# Battery_Prtection.net
KiCad netlist of a schematic drawn in Altium Designer
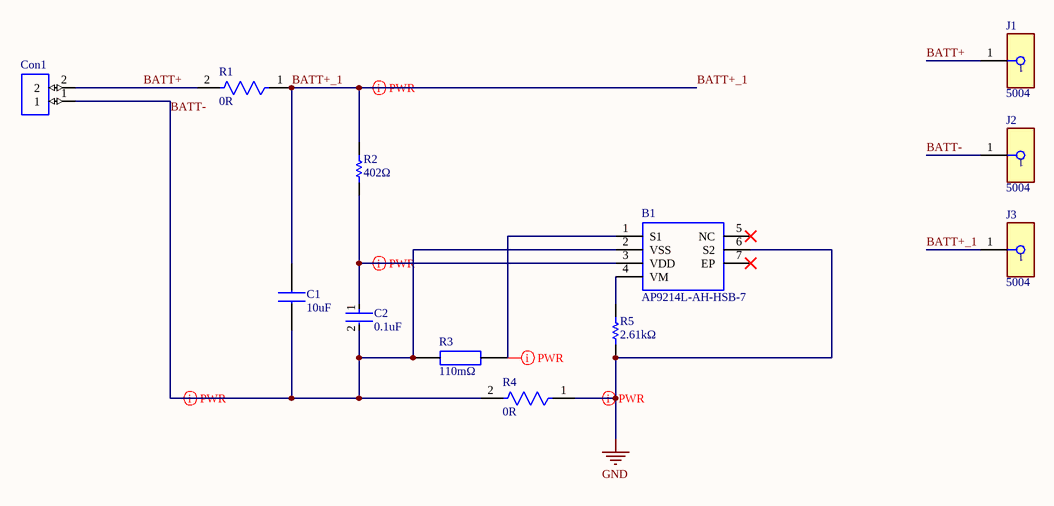
[diagram p0: Battery_Prtection.SchDoc]

(export (version "E")
  (design (tool "Eeschema 10.0.6"))
  (components
    (comp (ref "B1")
      (value "AP9214L-AH-HSB-7")
      (footprint "AP9214LAHHSB7")
      (description "Battery Management Sgl Chip Sol 1-Cell 30V Li Battery Mgt")
      (fields
        (field (name "MANUFACTURER") "Diodes Inc.")
        (field (name "MOUSER PART NUMBER") "621-AP9214L-AH-HSB-7")
      )
      (libsource (lib "AP9214L-AH-HSB-7") (part "AP9214L-AH-HSB-7"))
    )
    (comp (ref "C1")
      (value "10uF")
      (footprint "CAPC1005X70N")
      (description "CAP CER 10UF 6.3V X5R 0402")
      (fields
        (field (name "MANUFACTURER") "Samsung Electro-Mechanics")
        (field (name "MFR. PART #") "CL05A106MQ5NUNC")
      )
      (libsource (lib "CL05A106MQ5NUNC") (part "CL05A106MQ5NUNC"))
    )
    (comp (ref "C2")
      (value "0.1uF")
      (footprint "FP-CC0402-MFG")
      (description "CAP CER 0.1UF 16V X5R 0402")
      (fields
        (field (name "MFR. PART #") "CC0402KRX5R7BB104")
        (field (name "OCTOPART") "https://octopart.com/cc0402krx5r7bb104-yageo-8376508")
      )
      (libsource (lib "Altium Content Vault") (part "11868f565c42a9108669ba33697ecf6"))
    )
    (comp (ref "Con1")
      (value "SM02B-SRSS-TB(LF)(SN)")
      (footprint "SM02B-SRSS-TB(LF)(SN)")
      (description "Connector Header Surface Mount, Right Angle 2 position 0.039 _1.00mm_")
      (fields (field (name "MP") "SM02B-SRSS-TB_LF__SN_") (field (name "MF") "JST Sales"))
      (libsource (lib "SnapEDAsch") (part "SM02B-SRSS-TB(LF)(SN)"))
    )
    (comp (ref "J1")
      (value "5004")
      (footprint "FP-5004-MFG")
      (description "PC TEST POINT MINIATURE YELLOW")
      (fields
        (field (name "MANUFACTURER") "Keystone")
        (field (name "OCTOPART") "https://octopart.com/5004-keystone-28591")
      )
      (libsource (lib "Altium Content Vault") (part "98815daf2f2c152b0c43f5ab9800df6"))
    )
    (comp (ref "J2")
      (value "5004")
      (footprint "FP-5004-MFG")
      (description "PC TEST POINT MINIATURE YELLOW")
      (fields
        (field (name "MANUFACTURER") "Keystone")
        (field (name "OCTOPART") "https://octopart.com/5004-keystone-28591")
      )
      (libsource (lib "Altium Content Vault") (part "98815daf2f2c152b0c43f5ab9800df6"))
    )
    (comp (ref "J3")
      (value "5004")
      (footprint "FP-5004-MFG")
      (description "PC TEST POINT MINIATURE YELLOW")
      (fields
        (field (name "MANUFACTURER") "Keystone")
        (field (name "OCTOPART") "https://octopart.com/5004-keystone-28591")
      )
      (libsource (lib "Altium Content Vault") (part "98815daf2f2c152b0c43f5ab9800df6"))
    )
    (comp (ref "R1")
      (value "0R")
      (footprint "FP-RC0402-0_4-IPC_A")
      (description "RES SMD 0 OHM JUMPER 1/16W 0402")
      (fields (field (name "TOLERANCE") "1%") (field (name "LCSC PART #") "C106231"))
      (libsource (lib "Altium Content Vault") (part "1029c3af85768c4190bb7ad29bc67b5"))
    )
    (comp (ref "R2")
      (value "402Ω")
      (footprint "RESC1005X40X25LL05T10")
      (fields
        (field (name "MFR. PART #") "RC0402FR-07402RL")
        (field (name "MANUFACTURER") "Yageo")
        (field (name "LCSC PART #") "C137984")
      )
      (libsource (lib "Altium Content Vault") (part "RES"))
    )
    (comp (ref "R3")
      (value "110mΩ")
      (footprint "RESC6432X65N")
      (description "1W ±1% ±600ppm/℃ -55℃~+155℃ 110mΩ 2512 Chip Resistor - Surface Mount ROHS")
      (fields (field (name "MANUFACTURER") "YAGEO") (field (name "MFR. PART #") "RL2512FK-070R11L"))
      (libsource (lib "RL2512FK-070R11L") (part "RL2512FK-070R11L"))
    )
    (comp (ref "R4")
      (value "0R")
      (footprint "FP-RC0402-0_4-IPC_A")
      (description "RES SMD 0 OHM JUMPER 1/16W 0402")
      (fields (field (name "TOLERANCE") "1%") (field (name "LCSC PART #") "C106231"))
      (libsource (lib "Altium Content Vault") (part "1029c3af85768c4190bb7ad29bc67b5"))
    )
    (comp (ref "R5")
      (value "2.61kΩ")
      (footprint "RESC1005X40X25NL05T10")
      (fields
        (field (name "MANUFACTURER") "Yageo / Phycomp")
        (field (name "MFR. PART #") "RC0402FR-072K61L")
        (field (name "LCSC PART #") "C163472")
      )
      (libsource (lib "Altium Content Vault") (part "RES"))
    )
  )
  (nets
    (net (code "1") (name "/BATT+") (class "Default")
      (node (ref "Con1") (pin "2") (pinfunction "2_2") (pintype "bidirectional"))
      (node (ref "J1") (pin "1") (pinfunction "1_1") (pintype "passive"))
      (node (ref "R1") (pin "2") (pinfunction "2_2") (pintype "passive"))
    )
    (net (code "2") (name "/BATT+_1") (class "Default")
      (node (ref "C1") (pin "2") (pinfunction "2_2") (pintype "passive"))
      (node (ref "J3") (pin "1") (pinfunction "1_1") (pintype "passive"))
      (node (ref "R1") (pin "1") (pinfunction "1_1") (pintype "passive"))
      (node (ref "R2") (pin "2") (pinfunction "2_2") (pintype "passive"))
    )
    (net (code "3") (name "/BATT-") (class "Default")
      (node (ref "B1") (pin "2") (pinfunction "VSS_2") (pintype "passive"))
      (node (ref "C1") (pin "1") (pinfunction "1_1") (pintype "passive"))
      (node (ref "C2") (pin "2") (pinfunction "2_2") (pintype "passive"))
      (node (ref "Con1") (pin "1") (pinfunction "1_1") (pintype "bidirectional"))
      (node (ref "J2") (pin "1") (pinfunction "1_1") (pintype "passive"))
      (node (ref "R3") (pin "1") (pinfunction "1_1") (pintype "passive"))
      (node (ref "R4") (pin "2") (pinfunction "2_2") (pintype "passive"))
    )
    (net (code "4") (name "GND") (class "Default")
      (node (ref "B1") (pin "6") (pinfunction "S2_6") (pintype "passive"))
      (node (ref "R4") (pin "1") (pinfunction "1_1") (pintype "passive"))
      (node (ref "R5") (pin "1") (pinfunction "1_1") (pintype "passive"))
    )
    (net (code "5") (name "Net-(B1-S1)") (class "Default")
      (node (ref "B1") (pin "1") (pinfunction "S1_1") (pintype "passive"))
      (node (ref "R3") (pin "2") (pinfunction "2_2") (pintype "passive"))
    )
    (net (code "6") (name "Net-(B1-VDD)") (class "Default")
      (node (ref "B1") (pin "3") (pinfunction "VDD_3") (pintype "passive"))
      (node (ref "C2") (pin "1") (pinfunction "1_1") (pintype "passive"))
      (node (ref "R2") (pin "1") (pinfunction "1_1") (pintype "passive"))
    )
    (net (code "7") (name "Net-(B1-VM)") (class "Default")
      (node (ref "B1") (pin "4") (pinfunction "VM_4") (pintype "passive"))
      (node (ref "R5") (pin "2") (pinfunction "2_2") (pintype "passive"))
    )
    (net (code "8") (name "unconnected-(B1-EP-Pad7)") (class "Default")
      (node (ref "B1") (pin "7") (pinfunction "EP_7") (pintype "passive+no_connect"))
    )
    (net (code "9") (name "unconnected-(B1-NC-Pad5)") (class "Default")
      (node (ref "B1") (pin "5") (pinfunction "NC_5") (pintype "passive+no_connect"))
    )
  )
)
